# MCISO-S02-V00-12VProtection.net
KiCad netlist of a schematic drawn in Altium Designer
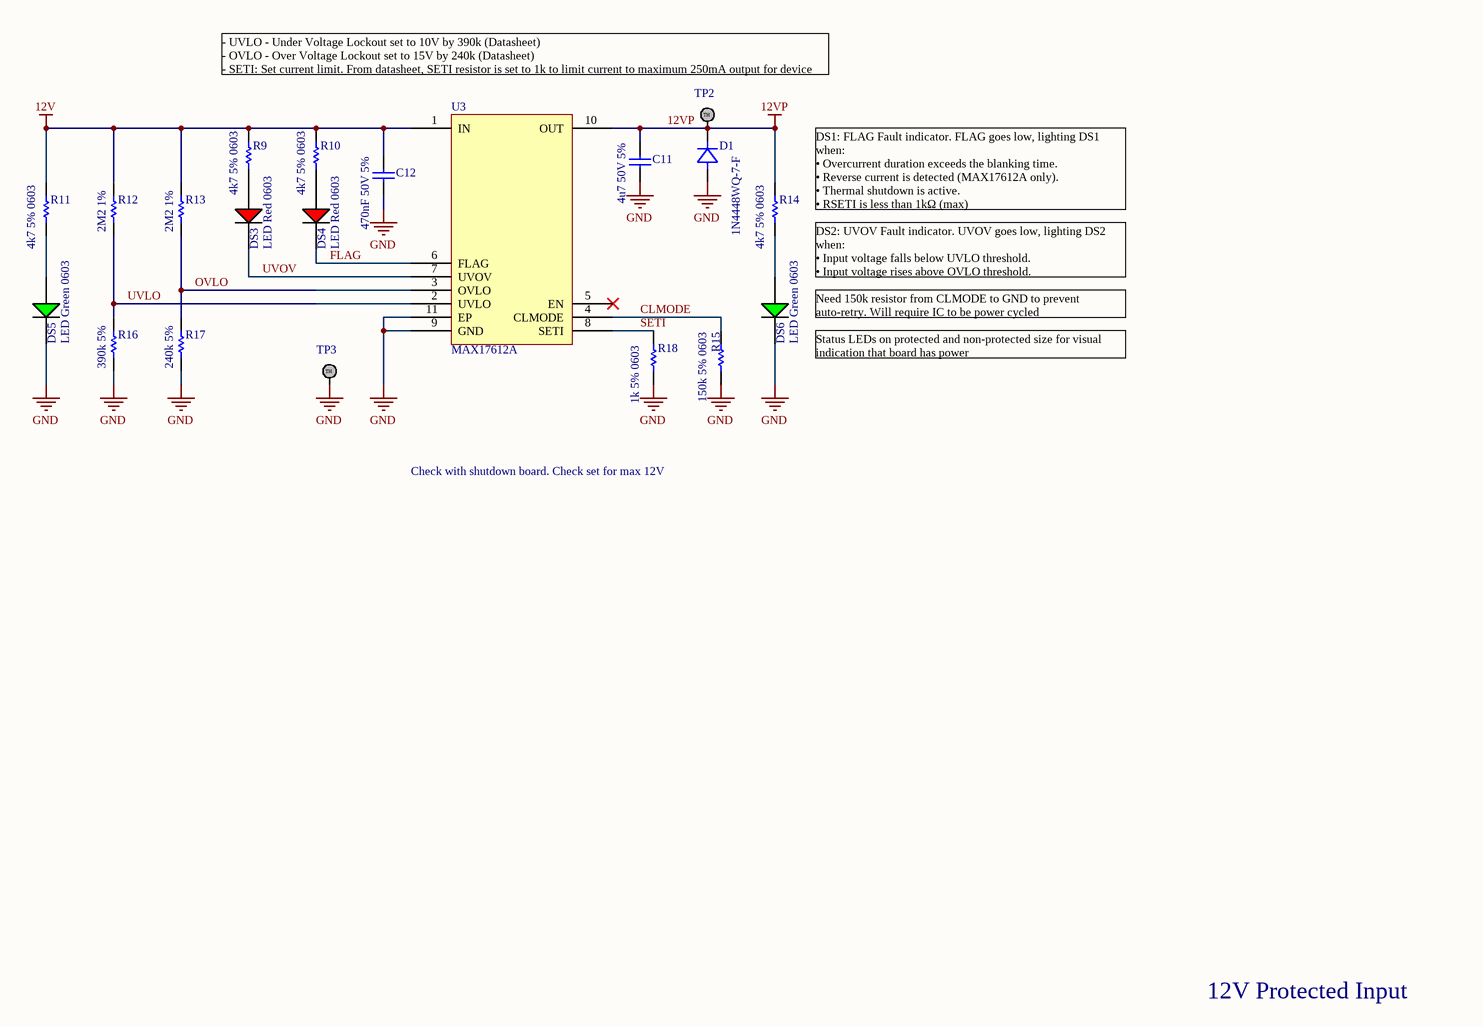
[diagram p0: MCISO-S02-V00-12VProtection.SchDoc]

(export (version "E")
  (design (tool "Eeschema 10.0.6"))
  (components
    (comp (ref "C11")
      (value "4u7 50V 5%")
      (footprint "Cap_Ceramic_0603")
      (description "Capacitor, Ceramic, SMD, 4u7, 50V, 5%, X7R, 0603")
      (libsource (lib "StandardCapacitors") (part "4u7 50V 5% X7R 0603"))
    )
    (comp (ref "C12")
      (value "470nF 50V 5%")
      (footprint "Cap_Ceramic_0603")
      (description "Capacitor, Ceramic, SMD, 470nF, 50V, 5%, X7R, 0603")
      (libsource (lib "StandardCapacitors") (part "470nF 50V 5% X7R 0603"))
    )
    (comp (ref "D1")
      (value "1N4448WQ-7-F")
      (footprint "SMA")
      (description "Diode, SMD, 75V, 5%, 250mA, SOD123")
      (fields
        (field (name "MANUFACTURER") "ON Semiconductor / Fairchild")
        (field (name "MANUFACTURER PART NUMBER") "1N914BWS")
      )
      (libsource (lib "QUTMS_DiodeLibrary") (part "1N4448WQ-7-F"))
    )
    (comp (ref "DS3")
      (value "LED Red 0603")
      (footprint "LED RED 0603")
      (libsource (lib "QUTMS_LEDLibrary") (part "LED Red 0603"))
    )
    (comp (ref "DS4")
      (value "LED Red 0603")
      (footprint "LED RED 0603")
      (libsource (lib "QUTMS_LEDLibrary") (part "LED Red 0603"))
    )
    (comp (ref "DS5")
      (value "LED Green 0603")
      (footprint "LED GREEN 0603")
      (libsource (lib "QUTMS_LEDLibrary") (part "LED Green 0603"))
    )
    (comp (ref "DS6")
      (value "LED Green 0603")
      (footprint "LED GREEN 0603")
      (libsource (lib "QUTMS_LEDLibrary") (part "LED Green 0603"))
    )
    (comp (ref "R9")
      (value "4k7 5% 0603")
      (footprint "Res_ThinFilm_0603")
      (description "Resistor, SMD, 4k7, 0.1W, 5%, 0603")
      (libsource (lib "StandardResistors") (part "4k7 5% 0603"))
    )
    (comp (ref "R10")
      (value "4k7 5% 0603")
      (footprint "Res_ThinFilm_0603")
      (description "Resistor, SMD, 4k7, 0.1W, 5%, 0603")
      (libsource (lib "StandardResistors") (part "4k7 5% 0603"))
    )
    (comp (ref "R11")
      (value "4k7 5% 0603")
      (footprint "Res_ThinFilm_0603")
      (description "Resistor, SMD, 4k7, 0.1W, 5%, 0603")
      (libsource (lib "StandardResistors") (part "4k7 5% 0603"))
    )
    (comp (ref "R12")
      (value "2M2 1%")
      (footprint "Res_ThinFilm_0603")
      (description "Resistor, SMD, 2M2, 0.125W, 1%, 0603")
      (libsource (lib "StandardResistors") (part "2M2 1% 0603"))
    )
    (comp (ref "R13")
      (value "2M2 1%")
      (footprint "Res_ThinFilm_0603")
      (description "Resistor, SMD, 2M2, 0.125W, 1%, 0603")
      (libsource (lib "StandardResistors") (part "2M2 1% 0603"))
    )
    (comp (ref "R14")
      (value "4k7 5% 0603")
      (footprint "Res_ThinFilm_0603")
      (description "Resistor, SMD, 4k7, 0.1W, 5%, 0603")
      (libsource (lib "StandardResistors") (part "4k7 5% 0603"))
    )
    (comp (ref "R15")
      (value "150k 5% 0603")
      (footprint "Res_ThinFilm_0603")
      (description "Resistor, SMD, 150k, 0.1W, 5%, 0603")
      (libsource (lib "StandardResistors") (part "150k 5%, 0603"))
    )
    (comp (ref "R16")
      (value "390k 5%")
      (footprint "Res_ThinFilm_0603")
      (description "Resistor, SMD, 390k, 0.1W, 5%, 0603")
      (libsource (lib "StandardResistors") (part "390k 5% 0603"))
    )
    (comp (ref "R17")
      (value "240k 5%")
      (footprint "Res_ThinFilm_0603")
      (description "Resistor, SMD, 240k, 0.1W, 5%, 0603")
      (libsource (lib "StandardResistors") (part "240k 5% 0603"))
    )
    (comp (ref "R18")
      (value "1k 5% 0603")
      (footprint "Res_ThinFilm_0603")
      (description "Resistor, SMD, 1k, 0.1W, 5%, 0603")
      (libsource (lib "StandardResistors") (part "1k 5% 0603"))
    )
    (comp (ref "TP2")
      (value "TestPoint")
      (footprint "TestPointSMD")
      (libsource (lib "StandardTest") (part "TestPoint"))
    )
    (comp (ref "TP3")
      (value "TestPoint")
      (footprint "TestPointSMD")
      (libsource (lib "StandardTest") (part "TestPoint"))
    )
    (comp (ref "U3")
      (value "MAX17612A")
      (footprint "MAX17612A")
      (description "4.5V to 60V, 250mA Current-Limiter with OV, UV, and Reverse Protection")
      (libsource (lib "QUTMS-MCISOLibrary") (part "MAX17612A"))
    )
  )
  (nets
    (net (code "1") (name "/CLMODE") (class "Default")
      (node (ref "R15") (pin "2") (pinfunction "2_2") (pintype "passive"))
      (node (ref "U3") (pin "4") (pinfunction "CLMODE_4") (pintype "passive"))
    )
    (net (code "2") (name "/FLAG") (class "Default")
      (node (ref "DS4") (pin "2") (pinfunction "C_2") (pintype "passive"))
      (node (ref "U3") (pin "6") (pinfunction "FLAG_6") (pintype "passive"))
    )
    (net (code "3") (name "/OVLO") (class "Default")
      (node (ref "R13") (pin "1") (pinfunction "1_1") (pintype "passive"))
      (node (ref "R17") (pin "2") (pinfunction "2_2") (pintype "passive"))
      (node (ref "U3") (pin "3") (pinfunction "OVLO_3") (pintype "passive"))
    )
    (net (code "4") (name "/SETI") (class "Default")
      (node (ref "R18") (pin "2") (pinfunction "2_2") (pintype "passive"))
      (node (ref "U3") (pin "8") (pinfunction "SETI_8") (pintype "passive"))
    )
    (net (code "5") (name "/UVLO") (class "Default")
      (node (ref "R12") (pin "1") (pinfunction "1_1") (pintype "passive"))
      (node (ref "R16") (pin "2") (pinfunction "2_2") (pintype "passive"))
      (node (ref "U3") (pin "2") (pinfunction "UVLO_2") (pintype "passive"))
    )
    (net (code "6") (name "/UVOV") (class "Default")
      (node (ref "DS3") (pin "2") (pinfunction "C_2") (pintype "passive"))
      (node (ref "U3") (pin "7") (pinfunction "UVOV_7") (pintype "passive"))
    )
    (net (code "7") (name "12V") (class "Default")
      (node (ref "C12") (pin "2") (pinfunction "2_2") (pintype "passive"))
      (node (ref "R10") (pin "2") (pinfunction "2_2") (pintype "passive"))
      (node (ref "R11") (pin "2") (pinfunction "2_2") (pintype "passive"))
      (node (ref "R12") (pin "2") (pinfunction "2_2") (pintype "passive"))
      (node (ref "R13") (pin "2") (pinfunction "2_2") (pintype "passive"))
      (node (ref "R9") (pin "2") (pinfunction "2_2") (pintype "passive"))
      (node (ref "U3") (pin "1") (pinfunction "IN_1") (pintype "passive"))
    )
    (net (code "8") (name "12VP") (class "Default")
      (node (ref "C11") (pin "2") (pinfunction "2_2") (pintype "passive"))
      (node (ref "D1") (pin "K") (pinfunction "Cathode_K") (pintype "passive"))
      (node (ref "R14") (pin "2") (pinfunction "2_2") (pintype "passive"))
      (node (ref "TP2") (pin "1") (pinfunction "1_1") (pintype "passive"))
      (node (ref "U3") (pin "10") (pinfunction "OUT_10") (pintype "passive"))
    )
    (net (code "9") (name "GND") (class "Default")
      (node (ref "C11") (pin "1") (pinfunction "1_1") (pintype "passive"))
      (node (ref "C12") (pin "1") (pinfunction "1_1") (pintype "passive"))
      (node (ref "D1") (pin "A") (pinfunction "Anode_A") (pintype "passive"))
      (node (ref "DS5") (pin "2") (pinfunction "C_2") (pintype "passive"))
      (node (ref "DS6") (pin "2") (pinfunction "C_2") (pintype "passive"))
      (node (ref "R15") (pin "1") (pinfunction "1_1") (pintype "passive"))
      (node (ref "R16") (pin "1") (pinfunction "1_1") (pintype "passive"))
      (node (ref "R17") (pin "1") (pinfunction "1_1") (pintype "passive"))
      (node (ref "R18") (pin "1") (pinfunction "1_1") (pintype "passive"))
      (node (ref "TP3") (pin "1") (pinfunction "1_1") (pintype "passive"))
      (node (ref "U3") (pin "11") (pinfunction "EP_11") (pintype "passive"))
      (node (ref "U3") (pin "9") (pinfunction "GND_9") (pintype "passive"))
    )
    (net (code "10") (name "Net-(DS3-A)") (class "Default")
      (node (ref "DS3") (pin "1") (pinfunction "A_1") (pintype "passive"))
      (node (ref "R9") (pin "1") (pinfunction "1_1") (pintype "passive"))
    )
    (net (code "11") (name "Net-(DS4-A)") (class "Default")
      (node (ref "DS4") (pin "1") (pinfunction "A_1") (pintype "passive"))
      (node (ref "R10") (pin "1") (pinfunction "1_1") (pintype "passive"))
    )
    (net (code "12") (name "Net-(DS5-A)") (class "Default")
      (node (ref "DS5") (pin "1") (pinfunction "A_1") (pintype "passive"))
      (node (ref "R11") (pin "1") (pinfunction "1_1") (pintype "passive"))
    )
    (net (code "13") (name "Net-(DS6-A)") (class "Default")
      (node (ref "DS6") (pin "1") (pinfunction "A_1") (pintype "passive"))
      (node (ref "R14") (pin "1") (pinfunction "1_1") (pintype "passive"))
    )
    (net (code "14") (name "unconnected-(U3-EN-Pad5)") (class "Default")
      (node (ref "U3") (pin "5") (pinfunction "EN_5") (pintype "passive+no_connect"))
    )
  )
)
